# Circulator_Board.net
KiCad netlist of a schematic drawn in EAGLE
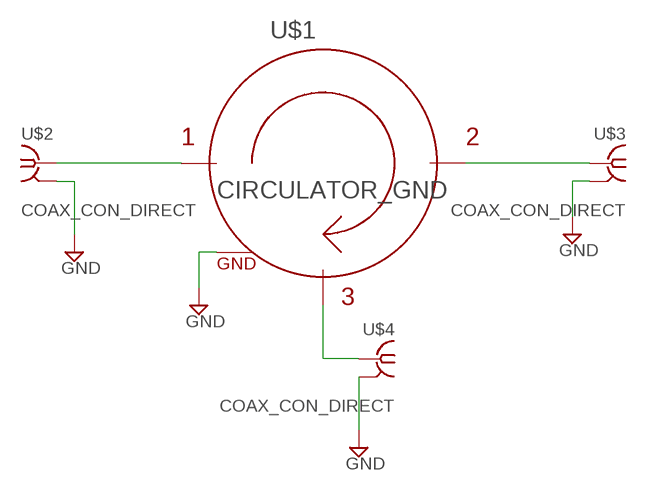
[diagram p0: schematic, sheet 1]

(export (version "E")
  (design (tool "Eeschema 10.0.6"))
  (components
    (comp (ref "U$1")
      (value "CIRCULATOR_GND")
      (footprint "eagle-import:JCD0126T0130LC100")
      (libsource (lib "eagle-import") (part "CIRCULATOR_GND"))
    )
    (comp (ref "U$2")
      (value "COAX_CON_DIRECT")
      (footprint "eagle-import:COAX.141")
      (libsource (lib "eagle-import") (part "COAX_CON_DIRECT"))
    )
    (comp (ref "U$3")
      (value "COAX_CON_DIRECT")
      (footprint "eagle-import:COAX.141")
      (libsource (lib "eagle-import") (part "COAX_CON_DIRECT"))
    )
    (comp (ref "U$4")
      (value "COAX_CON_DIRECT")
      (footprint "eagle-import:COAX.141")
      (libsource (lib "eagle-import") (part "COAX_CON_DIRECT"))
    )
  )
  (nets
    (net (code "1") (name "GND") (class "Default")
      (node (ref "U$1") (pin "P$1") (pinfunction "P$GND_P$1") (pintype "bidirectional"))
      (node (ref "U$1") (pin "P$2") (pinfunction "P$GND_P$2") (pintype "bidirectional"))
      (node (ref "U$1") (pin "P$3") (pinfunction "P$GND_P$3") (pintype "bidirectional"))
      (node (ref "U$1") (pin "P$4") (pinfunction "P$GND_P$4") (pintype "bidirectional"))
      (node (ref "U$2") (pin "P$2") (pinfunction "GND_P$2") (pintype "passive"))
      (node (ref "U$3") (pin "P$2") (pinfunction "GND_P$2") (pintype "passive"))
      (node (ref "U$4") (pin "P$2") (pinfunction "GND_P$2") (pintype "passive"))
    )
    (net (code "2") (name "Net-(U$1-P$1)") (class "Default")
      (node (ref "U$1") (pin "P$IN") (pinfunction "P$1_P$IN") (pintype "bidirectional"))
      (node (ref "U$2") (pin "P$1") (pinfunction "1_P$1") (pintype "passive"))
    )
    (net (code "3") (name "Net-(U$1-P$2)") (class "Default")
      (node (ref "U$1") (pin "P$OUT") (pinfunction "P$2_P$OUT") (pintype "bidirectional"))
      (node (ref "U$3") (pin "P$1") (pinfunction "1_P$1") (pintype "passive"))
    )
    (net (code "4") (name "Net-(U$1-P$3)") (class "Default")
      (node (ref "U$1") (pin "P$LOAD") (pinfunction "P$3_P$LOAD") (pintype "bidirectional"))
      (node (ref "U$4") (pin "P$1") (pinfunction "1_P$1") (pintype "passive"))
    )
  )
)
